# dongle.net
KiCad netlist of a schematic drawn in EAGLE
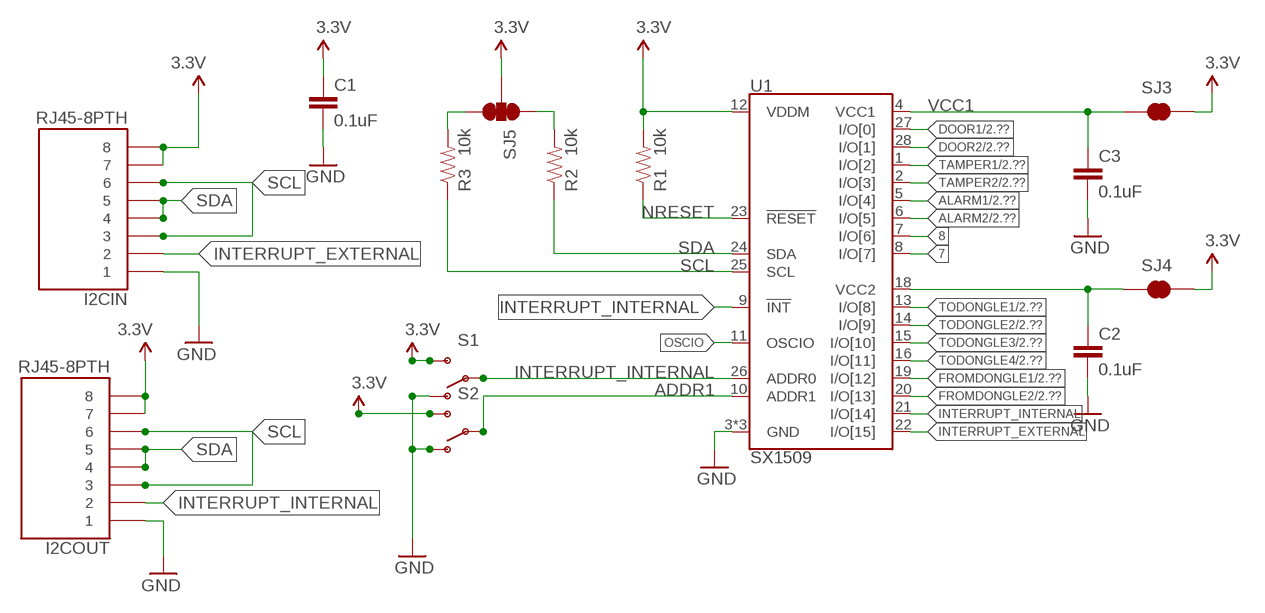
[diagram p0: schematic, sheet 1]
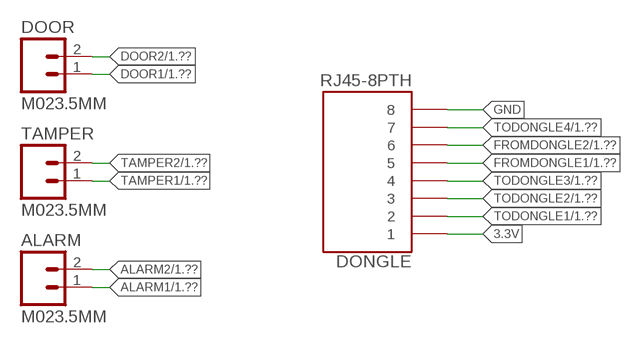
[diagram p1: schematic, sheet 2]

(export (version "E")
  (design (tool "Eeschema 10.0.6"))
  (components
    (comp (ref "ALARM")
      (value "M023.5MM")
      (footprint "eagle-import:SCREWTERMINAL-3.5MM-2")
      (libsource (lib "eagle-import") (part "M023.5MM"))
    )
    (comp (ref "DONGLE")
      (value "RJ45-8PTH")
      (footprint "eagle-import:RJ45-8")
      (libsource (lib "eagle-import") (part "RJ45-8PTH"))
    )
    (comp (ref "DOOR")
      (value "M023.5MM")
      (footprint "eagle-import:SCREWTERMINAL-3.5MM-2")
      (libsource (lib "eagle-import") (part "M023.5MM"))
    )
    (comp (ref "TAMPER")
      (value "M023.5MM")
      (footprint "eagle-import:SCREWTERMINAL-3.5MM-2")
      (libsource (lib "eagle-import") (part "M023.5MM"))
    )
    (comp (ref "C1")
      (value "0.1uF")
      (footprint "eagle-import:0402-CAP")
      (libsource (lib "eagle-import") (part "CAP0402-CAP"))
    )
    (comp (ref "C2")
      (value "0.1uF")
      (footprint "eagle-import:0402-CAP")
      (libsource (lib "eagle-import") (part "CAP0402-CAP"))
    )
    (comp (ref "C3")
      (value "0.1uF")
      (footprint "eagle-import:0402-CAP")
      (libsource (lib "eagle-import") (part "CAP0402-CAP"))
    )
    (comp (ref "I2CIN")
      (value "RJ45-8PTH")
      (footprint "eagle-import:RJ45-8")
      (libsource (lib "eagle-import") (part "RJ45-8PTH"))
    )
    (comp (ref "I2COUT")
      (value "RJ45-8PTH")
      (footprint "eagle-import:RJ45-8")
      (libsource (lib "eagle-import") (part "RJ45-8PTH"))
    )
    (comp (ref "R1")
      (value "10k")
      (footprint "eagle-import:0402-RES")
      (libsource (lib "eagle-import") (part "RESISTOR0402-RES"))
    )
    (comp (ref "R2")
      (value "10k")
      (footprint "eagle-import:0402-RES")
      (libsource (lib "eagle-import") (part "RESISTOR0402-RES"))
    )
    (comp (ref "R3")
      (value "10k")
      (footprint "eagle-import:0402-RES")
      (libsource (lib "eagle-import") (part "RESISTOR0402-RES"))
    )
    (comp (ref "S1")
      (value "SWITCH-SPDT-SMD-A")
      (footprint "eagle-import:SWITCH-SPST-SMD-A")
      (libsource (lib "eagle-import") (part "SWITCH-SPDT-SMD-A"))
    )
    (comp (ref "S2")
      (value "SWITCH-SPDT-SMD-A")
      (footprint "eagle-import:SWITCH-SPST-SMD-A")
      (libsource (lib "eagle-import") (part "SWITCH-SPDT-SMD-A"))
    )
    (comp (ref "SJ3")
      (value "SOLDERJUMPERNO")
      (footprint "eagle-import:SJ_2S-NO")
      (libsource (lib "eagle-import") (part "SOLDERJUMPERNO"))
    )
    (comp (ref "SJ4")
      (value "SOLDERJUMPERNO")
      (footprint "eagle-import:SJ_2S-NO")
      (libsource (lib "eagle-import") (part "SOLDERJUMPERNO"))
    )
    (comp (ref "SJ5")
      (value "SOLDERJUMPER_2WAYS")
      (footprint "eagle-import:SJ_3")
      (libsource (lib "eagle-import") (part "SOLDERJUMPER_2WAYS"))
    )
    (comp (ref "U1")
      (value "SX1509")
      (footprint "eagle-import:QFN-28")
      (libsource (lib "eagle-import") (part "SX1509"))
    )
  )
  (nets
    (net (code "1") (name "3.3V") (class "Default")
      (node (ref "C1") (pin "1") (pinfunction "1_1") (pintype "passive"))
      (node (ref "DONGLE") (pin "1") (pinfunction "1_1") (pintype "bidirectional"))
      (node (ref "I2CIN") (pin "7") (pinfunction "7_7") (pintype "bidirectional"))
      (node (ref "I2CIN") (pin "8") (pinfunction "8_8") (pintype "bidirectional"))
      (node (ref "I2COUT") (pin "7") (pinfunction "7_7") (pintype "bidirectional"))
      (node (ref "I2COUT") (pin "8") (pinfunction "8_8") (pintype "bidirectional"))
      (node (ref "R1") (pin "2") (pinfunction "2_2") (pintype "passive"))
      (node (ref "S1") (pin "3") (pinfunction "S_3") (pintype "passive"))
      (node (ref "S2") (pin "3") (pinfunction "S_3") (pintype "passive"))
      (node (ref "SJ3") (pin "2") (pinfunction "2_2") (pintype "passive"))
      (node (ref "SJ4") (pin "2") (pinfunction "2_2") (pintype "passive"))
      (node (ref "SJ5") (pin "2") (pinfunction "2_2") (pintype "passive"))
      (node (ref "U1") (pin "12") (pinfunction "VDDM_12") (pintype "bidirectional"))
    )
    (net (code "2") (name "7") (class "Default")
      (node (ref "U1") (pin "8") (pinfunction "I/O[7]_8") (pintype "bidirectional"))
    )
    (net (code "3") (name "8") (class "Default")
      (node (ref "U1") (pin "7") (pinfunction "I/O[6]_7") (pintype "bidirectional"))
    )
    (net (code "4") (name "ADDR1") (class "Default")
      (node (ref "S2") (pin "2") (pinfunction "P_2") (pintype "passive"))
      (node (ref "U1") (pin "10") (pinfunction "ADDR1_10") (pintype "bidirectional"))
    )
    (net (code "5") (name "ALARM1") (class "Default")
      (node (ref "ALARM") (pin "1") (pinfunction "1_1") (pintype "passive"))
      (node (ref "U1") (pin "5") (pinfunction "I/O[4]_5") (pintype "bidirectional"))
    )
    (net (code "6") (name "ALARM2") (class "Default")
      (node (ref "ALARM") (pin "2") (pinfunction "2_2") (pintype "passive"))
      (node (ref "U1") (pin "6") (pinfunction "I/O[5]_6") (pintype "bidirectional"))
    )
    (net (code "7") (name "DOOR1") (class "Default")
      (node (ref "DOOR") (pin "1") (pinfunction "1_1") (pintype "passive"))
      (node (ref "U1") (pin "27") (pinfunction "I/O[0]_27") (pintype "bidirectional"))
    )
    (net (code "8") (name "DOOR2") (class "Default")
      (node (ref "DOOR") (pin "2") (pinfunction "2_2") (pintype "passive"))
      (node (ref "U1") (pin "28") (pinfunction "I/O[1]_28") (pintype "bidirectional"))
    )
    (net (code "9") (name "FROMDONGLE1") (class "Default")
      (node (ref "DONGLE") (pin "5") (pinfunction "5_5") (pintype "bidirectional"))
      (node (ref "U1") (pin "19") (pinfunction "I/O[12]_19") (pintype "bidirectional"))
    )
    (net (code "10") (name "FROMDONGLE2") (class "Default")
      (node (ref "DONGLE") (pin "6") (pinfunction "6_6") (pintype "bidirectional"))
      (node (ref "U1") (pin "20") (pinfunction "I/O[13]_20") (pintype "bidirectional"))
    )
    (net (code "11") (name "GND") (class "Default")
      (node (ref "C1") (pin "2") (pinfunction "2_2") (pintype "passive"))
      (node (ref "C2") (pin "2") (pinfunction "2_2") (pintype "passive"))
      (node (ref "C3") (pin "2") (pinfunction "2_2") (pintype "passive"))
      (node (ref "DONGLE") (pin "8") (pinfunction "8_8") (pintype "bidirectional"))
      (node (ref "I2CIN") (pin "1") (pinfunction "1_1") (pintype "bidirectional"))
      (node (ref "I2COUT") (pin "1") (pinfunction "1_1") (pintype "bidirectional"))
      (node (ref "S1") (pin "1") (pinfunction "O_1") (pintype "passive"))
      (node (ref "S2") (pin "1") (pinfunction "O_1") (pintype "passive"))
      (node (ref "U1") (pin "17") (pinfunction "GND_17") (pintype "bidirectional"))
      (node (ref "U1") (pin "29") (pinfunction "GND_29") (pintype "bidirectional"))
      (node (ref "U1") (pin "3") (pinfunction "GND_3") (pintype "bidirectional"))
    )
    (net (code "12") (name "INTERRUPT_EXTERNAL") (class "Default")
      (node (ref "I2CIN") (pin "2") (pinfunction "2_2") (pintype "bidirectional"))
      (node (ref "U1") (pin "22") (pinfunction "I/O[15]_22") (pintype "bidirectional"))
    )
    (net (code "13") (name "INTERRUPT_INTERNAL") (class "Default")
      (node (ref "I2COUT") (pin "2") (pinfunction "2_2") (pintype "bidirectional"))
      (node (ref "S1") (pin "2") (pinfunction "P_2") (pintype "passive"))
      (node (ref "U1") (pin "21") (pinfunction "I/O[14]_21") (pintype "bidirectional"))
      (node (ref "U1") (pin "26") (pinfunction "ADDR0_26") (pintype "bidirectional"))
      (node (ref "U1") (pin "9") (pinfunction "~{INT}_9") (pintype "bidirectional"))
    )
    (net (code "14") (name "NRESET") (class "Default")
      (node (ref "R1") (pin "1") (pinfunction "1_1") (pintype "passive"))
      (node (ref "U1") (pin "23") (pinfunction "~{RESET}_23") (pintype "bidirectional"))
    )
    (net (code "15") (name "Net-(R2-Pad2)") (class "Default")
      (node (ref "R2") (pin "2") (pinfunction "2_2") (pintype "passive"))
      (node (ref "SJ5") (pin "1") (pinfunction "1_1") (pintype "passive"))
    )
    (net (code "16") (name "Net-(R3-Pad2)") (class "Default")
      (node (ref "R3") (pin "2") (pinfunction "2_2") (pintype "passive"))
      (node (ref "SJ5") (pin "3") (pinfunction "3_3") (pintype "passive"))
    )
    (net (code "17") (name "Net-(U1-VCC2)") (class "Default")
      (node (ref "C2") (pin "1") (pinfunction "1_1") (pintype "passive"))
      (node (ref "SJ4") (pin "1") (pinfunction "1_1") (pintype "passive"))
      (node (ref "U1") (pin "18") (pinfunction "VCC2_18") (pintype "bidirectional"))
    )
    (net (code "18") (name "OSCIO") (class "Default")
      (node (ref "U1") (pin "11") (pinfunction "OSCIO_11") (pintype "bidirectional"))
    )
    (net (code "19") (name "SCL") (class "Default")
      (node (ref "I2CIN") (pin "3") (pinfunction "3_3") (pintype "bidirectional"))
      (node (ref "I2CIN") (pin "6") (pinfunction "6_6") (pintype "bidirectional"))
      (node (ref "I2COUT") (pin "3") (pinfunction "3_3") (pintype "bidirectional"))
      (node (ref "I2COUT") (pin "6") (pinfunction "6_6") (pintype "bidirectional"))
      (node (ref "R3") (pin "1") (pinfunction "1_1") (pintype "passive"))
      (node (ref "U1") (pin "25") (pinfunction "SCL_25") (pintype "bidirectional"))
    )
    (net (code "20") (name "SDA") (class "Default")
      (node (ref "I2CIN") (pin "4") (pinfunction "4_4") (pintype "bidirectional"))
      (node (ref "I2CIN") (pin "5") (pinfunction "5_5") (pintype "bidirectional"))
      (node (ref "I2COUT") (pin "4") (pinfunction "4_4") (pintype "bidirectional"))
      (node (ref "I2COUT") (pin "5") (pinfunction "5_5") (pintype "bidirectional"))
      (node (ref "R2") (pin "1") (pinfunction "1_1") (pintype "passive"))
      (node (ref "U1") (pin "24") (pinfunction "SDA_24") (pintype "bidirectional"))
    )
    (net (code "21") (name "TAMPER1") (class "Default")
      (node (ref "TAMPER") (pin "1") (pinfunction "1_1") (pintype "passive"))
      (node (ref "U1") (pin "1") (pinfunction "I/O[2]_1") (pintype "bidirectional"))
    )
    (net (code "22") (name "TAMPER2") (class "Default")
      (node (ref "TAMPER") (pin "2") (pinfunction "2_2") (pintype "passive"))
      (node (ref "U1") (pin "2") (pinfunction "I/O[3]_2") (pintype "bidirectional"))
    )
    (net (code "23") (name "TODONGLE1") (class "Default")
      (node (ref "DONGLE") (pin "2") (pinfunction "2_2") (pintype "bidirectional"))
      (node (ref "U1") (pin "13") (pinfunction "I/O[8]_13") (pintype "bidirectional"))
    )
    (net (code "24") (name "TODONGLE2") (class "Default")
      (node (ref "DONGLE") (pin "3") (pinfunction "3_3") (pintype "bidirectional"))
      (node (ref "U1") (pin "14") (pinfunction "I/O[9]_14") (pintype "bidirectional"))
    )
    (net (code "25") (name "TODONGLE3") (class "Default")
      (node (ref "DONGLE") (pin "4") (pinfunction "4_4") (pintype "bidirectional"))
      (node (ref "U1") (pin "15") (pinfunction "I/O[10]_15") (pintype "bidirectional"))
    )
    (net (code "26") (name "TODONGLE4") (class "Default")
      (node (ref "DONGLE") (pin "7") (pinfunction "7_7") (pintype "bidirectional"))
      (node (ref "U1") (pin "16") (pinfunction "I/O[11]_16") (pintype "bidirectional"))
    )
    (net (code "27") (name "VCC1") (class "Default")
      (node (ref "C3") (pin "1") (pinfunction "1_1") (pintype "passive"))
      (node (ref "SJ3") (pin "1") (pinfunction "1_1") (pintype "passive"))
      (node (ref "U1") (pin "4") (pinfunction "VCC1_4") (pintype "bidirectional"))
    )
  )
)
